# NEJE-KZ-board.net
KiCad netlist of a schematic drawn in EAGLE
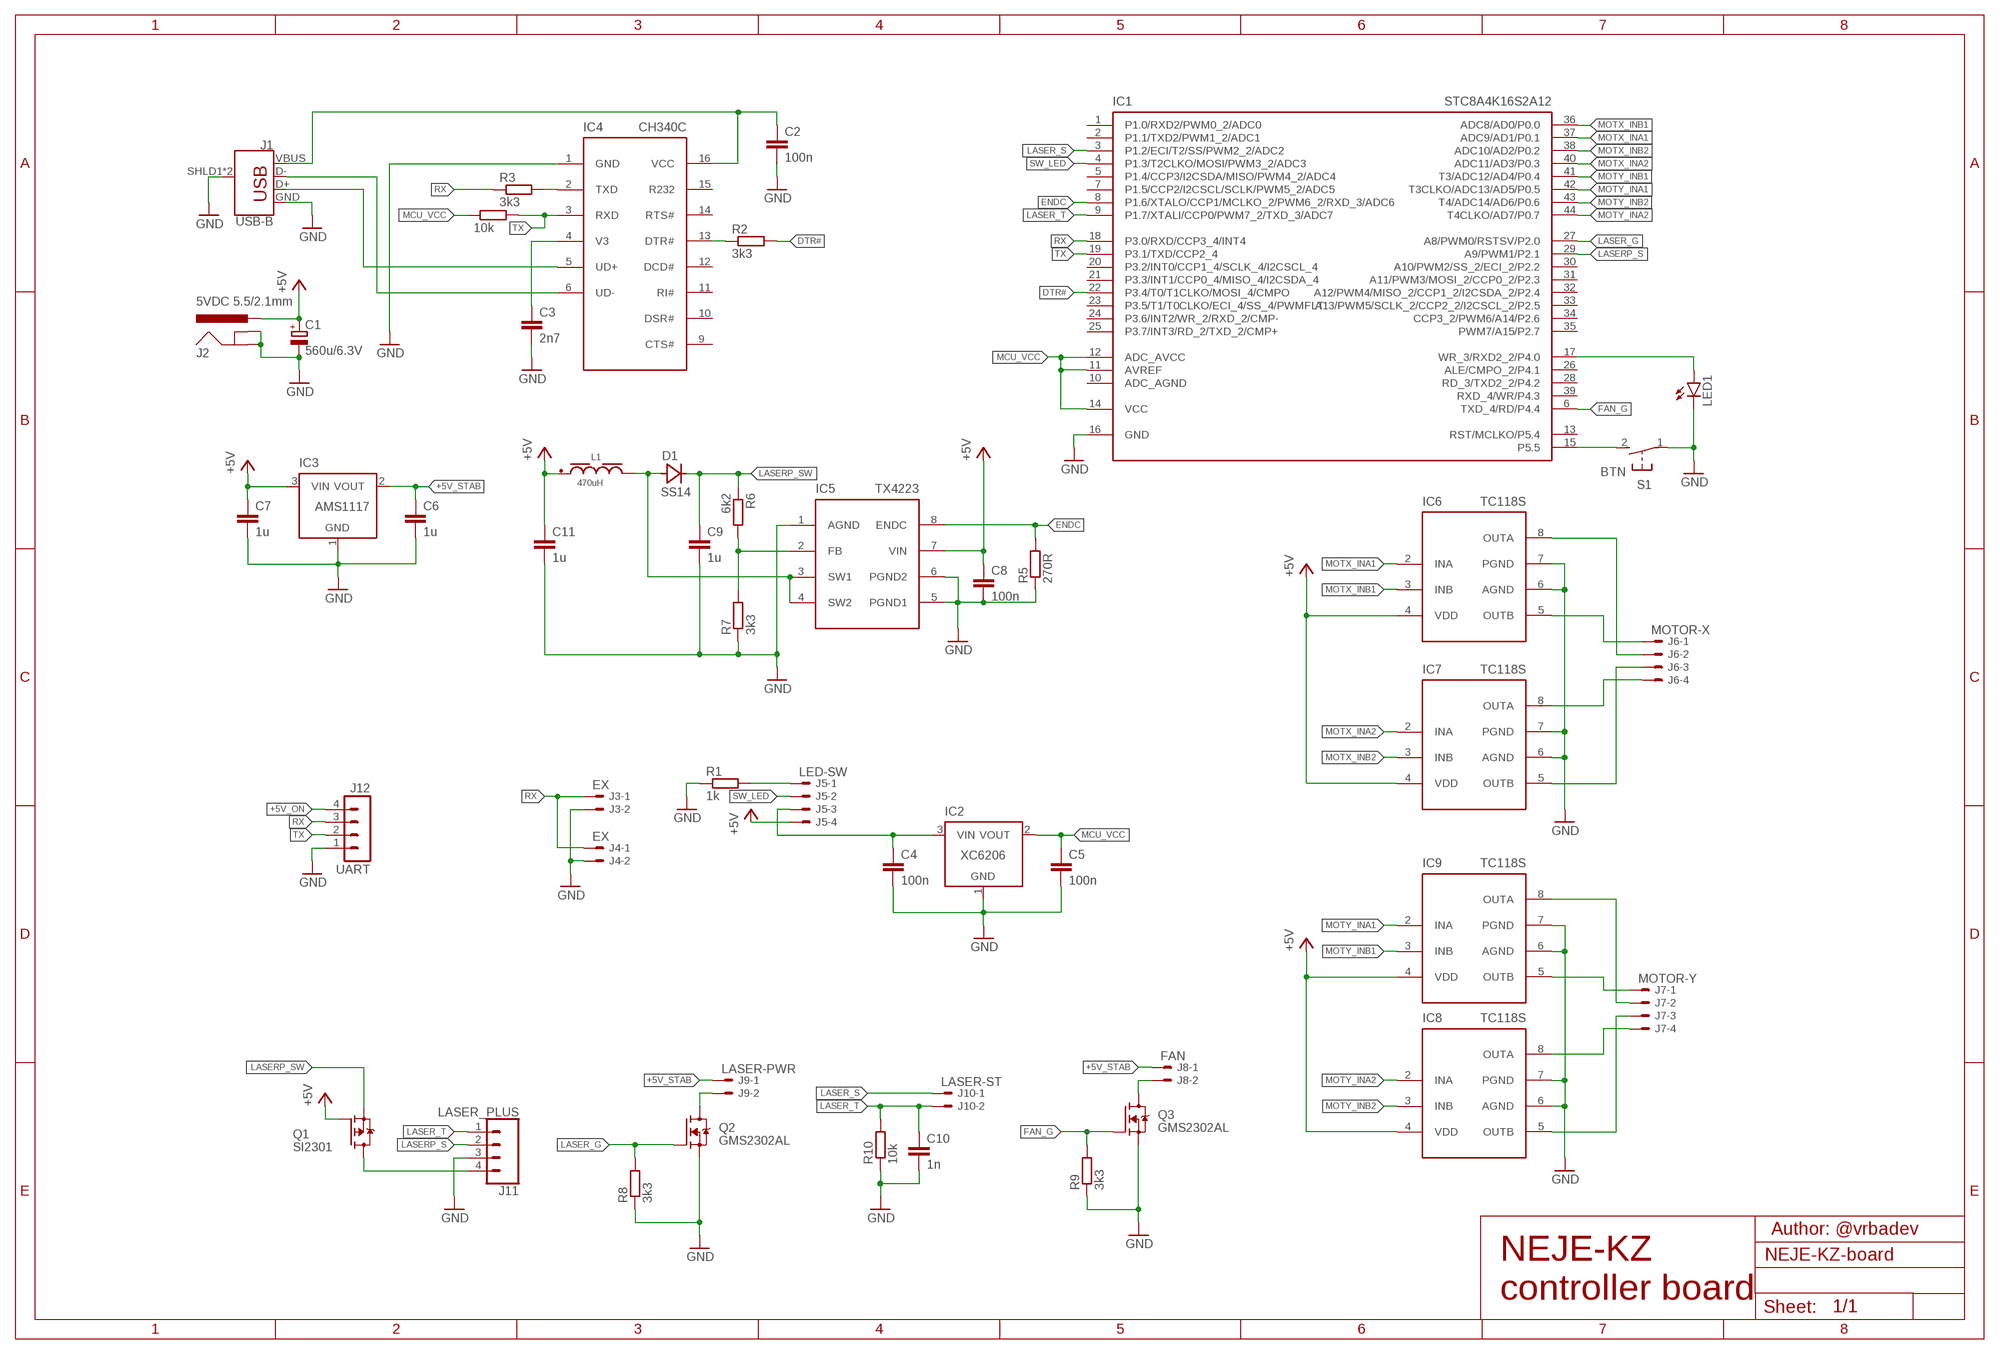
[diagram p0: schematic, sheet 1]

(export (version "E")
  (design (tool "Eeschema 10.0.6"))
  (components
    (comp (ref "C1")
      (value "560u/6.3V")
      (footprint "eagle-import:E2,5-7")
      (libsource (lib "eagle-import") (part "CPOL-EUE2.5-7"))
    )
    (comp (ref "C2")
      (value "100n")
      (footprint "eagle-import:C0402")
      (libsource (lib "eagle-import") (part "C-EUC0402"))
    )
    (comp (ref "C3")
      (value "2n7")
      (footprint "eagle-import:C0402")
      (libsource (lib "eagle-import") (part "C-EUC0402"))
    )
    (comp (ref "C4")
      (value "100n")
      (footprint "eagle-import:C0402")
      (libsource (lib "eagle-import") (part "C-EUC0402"))
    )
    (comp (ref "C5")
      (value "100n")
      (footprint "eagle-import:C0402")
      (libsource (lib "eagle-import") (part "C-EUC0402"))
    )
    (comp (ref "C6")
      (value "1u")
      (footprint "eagle-import:C0603")
      (libsource (lib "eagle-import") (part "C-EUC0603"))
    )
    (comp (ref "C7")
      (value "1u")
      (footprint "eagle-import:C0603")
      (libsource (lib "eagle-import") (part "C-EUC0603"))
    )
    (comp (ref "C8")
      (value "100n")
      (footprint "eagle-import:C0402")
      (libsource (lib "eagle-import") (part "C-EUC0402"))
    )
    (comp (ref "C9")
      (value "1u")
      (footprint "eagle-import:C0805")
      (libsource (lib "eagle-import") (part "C-EUC0805"))
    )
    (comp (ref "C10")
      (value "1n")
      (footprint "eagle-import:C0402")
      (libsource (lib "eagle-import") (part "C-EUC0402"))
    )
    (comp (ref "C11")
      (value "1u")
      (footprint "eagle-import:C0805")
      (libsource (lib "eagle-import") (part "C-EUC0805"))
    )
    (comp (ref "D1")
      (value "SS14")
      (footprint "eagle-import:SMA")
      (libsource (lib "eagle-import") (part "MBRA340T3"))
    )
    (comp (ref "IC1")
      (value "STC8A4K16S2A12")
      (footprint "eagle-import:LQFP44-10X10")
      (libsource (lib "eagle-import") (part "STC8A4K16S2A12"))
    )
    (comp (ref "IC2")
      (value "XC6206")
      (footprint "eagle-import:SOT23-3")
      (libsource (lib "eagle-import") (part "XC6206"))
    )
    (comp (ref "IC3")
      (value "AMS1117")
      (footprint "eagle-import:SOT223")
      (libsource (lib "eagle-import") (part "AMS1117"))
    )
    (comp (ref "IC4")
      (value "CH340C")
      (footprint "eagle-import:SO16")
      (libsource (lib "eagle-import") (part "CH340C"))
    )
    (comp (ref "IC5")
      (value "TX4223")
      (footprint "eagle-import:SOIC8")
      (libsource (lib "eagle-import") (part "TX4223"))
    )
    (comp (ref "IC6")
      (value "TC118S")
      (footprint "eagle-import:SOIC8")
      (libsource (lib "eagle-import") (part "TC118S"))
    )
    (comp (ref "IC7")
      (value "TC118S")
      (footprint "eagle-import:SOIC8")
      (libsource (lib "eagle-import") (part "TC118S"))
    )
    (comp (ref "IC8")
      (value "TC118S")
      (footprint "eagle-import:SOIC8")
      (libsource (lib "eagle-import") (part "TC118S"))
    )
    (comp (ref "IC9")
      (value "TC118S")
      (footprint "eagle-import:SOIC8")
      (libsource (lib "eagle-import") (part "TC118S"))
    )
    (comp (ref "J1")
      (value "USB-B")
      (footprint "eagle-import:USB-B-PTH")
      (libsource (lib "eagle-import") (part "USB_B_PTH"))
    )
    (comp (ref "J2")
      (value "5VDC 5.5/2.1mm")
      (footprint "eagle-import:POWER_JACK_SLOT")
      (libsource (lib "eagle-import") (part "POWER_JACKSLT"))
    )
    (comp (ref "J3")
      (value "EX")
      (footprint "eagle-import:JST-XH-02-PACKAGE-LONG-PAD")
      (libsource (lib "eagle-import") (part "JST-XH-02-PIN-LONG-PAD"))
    )
    (comp (ref "J4")
      (value "EX")
      (footprint "eagle-import:JST-XH-02-PACKAGE-LONG-PAD")
      (libsource (lib "eagle-import") (part "JST-XH-02-PIN-LONG-PAD"))
    )
    (comp (ref "J5")
      (value "LED-SW")
      (footprint "eagle-import:JST-XH-04-PACKAGE-LONG-PAD")
      (libsource (lib "eagle-import") (part "JST-XH-04-PIN-LONG-PAD"))
    )
    (comp (ref "J6")
      (value "MOTOR-X")
      (footprint "eagle-import:JST-XH-04-PACKAGE-LONG-PAD")
      (libsource (lib "eagle-import") (part "JST-XH-04-PIN-LONG-PAD"))
    )
    (comp (ref "J7")
      (value "MOTOR-Y")
      (footprint "eagle-import:JST-XH-04-PACKAGE-LONG-PAD")
      (libsource (lib "eagle-import") (part "JST-XH-04-PIN-LONG-PAD"))
    )
    (comp (ref "J8")
      (value "FAN")
      (footprint "eagle-import:JST-XH-02-PACKAGE-LONG-PAD")
      (libsource (lib "eagle-import") (part "JST-XH-02-PIN-LONG-PAD"))
    )
    (comp (ref "J9")
      (value "LASER-PWR")
      (footprint "eagle-import:JST-XH-02-PACKAGE-LONG-PAD")
      (libsource (lib "eagle-import") (part "JST-XH-02-PIN-LONG-PAD"))
    )
    (comp (ref "J10")
      (value "LASER-ST")
      (footprint "eagle-import:JST-XH-02-PACKAGE-LONG-PAD")
      (libsource (lib "eagle-import") (part "JST-XH-02-PIN-LONG-PAD"))
    )
    (comp (ref "J11")
      (value "LASER_PLUS")
      (footprint "eagle-import:1X04_1MM_RA")
      (libsource (lib "eagle-import") (part "CONN_04SMD2"))
    )
    (comp (ref "J12")
      (value "UART")
      (footprint "eagle-import:MA04-1")
      (libsource (lib "eagle-import") (part "MA04-1"))
    )
    (comp (ref "L1")
      (value "470uH")
      (footprint "eagle-import:WE-PD_7345")
      (libsource (lib "eagle-import") (part "WE-PD_7345_74477724"))
    )
    (comp (ref "LED1")
      (value "LEDCHIP-LED0805")
      (footprint "eagle-import:CHIP-LED0805")
      (libsource (lib "eagle-import") (part "LEDCHIP-LED0805"))
    )
    (comp (ref "Q1")
      (value "SI2301")
      (footprint "eagle-import:SOT23-3")
      (libsource (lib "eagle-import") (part "SI2301"))
    )
    (comp (ref "Q2")
      (value "GMS2302AL")
      (footprint "eagle-import:SOT23-3")
      (libsource (lib "eagle-import") (part "GMS2302AL"))
    )
    (comp (ref "Q3")
      (value "GMS2302AL")
      (footprint "eagle-import:SOT23-3")
      (libsource (lib "eagle-import") (part "GMS2302AL"))
    )
    (comp (ref "R1")
      (value "1k")
      (footprint "eagle-import:R0402")
      (libsource (lib "eagle-import") (part "R-EU_R0402"))
    )
    (comp (ref "R2")
      (value "3k3")
      (footprint "eagle-import:R0402")
      (libsource (lib "eagle-import") (part "R-EU_R0402"))
    )
    (comp (ref "R3")
      (value "3k3")
      (footprint "eagle-import:R0402")
      (libsource (lib "eagle-import") (part "R-EU_R0402"))
    )
    (comp (ref "R4")
      (value "10k")
      (footprint "eagle-import:R0402")
      (libsource (lib "eagle-import") (part "R-EU_R0402"))
    )
    (comp (ref "R5")
      (value "270R")
      (footprint "eagle-import:R0402")
      (libsource (lib "eagle-import") (part "R-EU_R0402"))
    )
    (comp (ref "R6")
      (value "6k2")
      (footprint "eagle-import:R0402")
      (libsource (lib "eagle-import") (part "R-EU_R0402"))
    )
    (comp (ref "R7")
      (value "3k3")
      (footprint "eagle-import:R0402")
      (libsource (lib "eagle-import") (part "R-EU_R0402"))
    )
    (comp (ref "R8")
      (value "3k3")
      (footprint "eagle-import:R0402")
      (libsource (lib "eagle-import") (part "R-EU_R0402"))
    )
    (comp (ref "R9")
      (value "3k3")
      (footprint "eagle-import:R0402")
      (libsource (lib "eagle-import") (part "R-EU_R0402"))
    )
    (comp (ref "R10")
      (value "10k")
      (footprint "eagle-import:R0402")
      (libsource (lib "eagle-import") (part "R-EU_R0402"))
    )
    (comp (ref "S1")
      (value "BTN")
      (footprint "eagle-import:DTSM-3")
      (libsource (lib "eagle-import") (part "DTSM-3"))
    )
  )
  (nets
    (net (code "1") (name "+5V") (class "Default")
      (node (ref "C1") (pin "+") (pinfunction "+_+") (pintype "passive"))
      (node (ref "C11") (pin "1") (pinfunction "1_1") (pintype "passive"))
      (node (ref "C7") (pin "1") (pinfunction "1_1") (pintype "passive"))
      (node (ref "C8") (pin "1") (pinfunction "1_1") (pintype "passive"))
      (node (ref "IC3") (pin "3") (pinfunction "VIN_3") (pintype "passive"))
      (node (ref "IC5") (pin "7") (pinfunction "VIN_7") (pintype "bidirectional"))
      (node (ref "IC6") (pin "4") (pinfunction "VDD_4") (pintype "bidirectional"))
      (node (ref "IC7") (pin "4") (pinfunction "VDD_4") (pintype "bidirectional"))
      (node (ref "IC8") (pin "4") (pinfunction "VDD_4") (pintype "bidirectional"))
      (node (ref "IC9") (pin "4") (pinfunction "VDD_4") (pintype "bidirectional"))
      (node (ref "J2") (pin "PWR") (pinfunction "PWR_PWR") (pintype "power_in"))
      (node (ref "J5") (pin "4") (pinfunction "S_4") (pintype "passive"))
      (node (ref "L1") (pin "1") (pinfunction "1_1") (pintype "passive"))
      (node (ref "Q1") (pin "1") (pinfunction "G_1") (pintype "passive"))
    )
    (net (code "2") (name "+5V_ON") (class "Default")
      (node (ref "C4") (pin "1") (pinfunction "1_1") (pintype "passive"))
      (node (ref "IC2") (pin "3") (pinfunction "VIN_3") (pintype "passive"))
      (node (ref "J12") (pin "4") (pinfunction "4_4") (pintype "passive"))
      (node (ref "J5") (pin "3") (pinfunction "S_3") (pintype "passive"))
    )
    (net (code "3") (name "+5V_STAB") (class "Default")
      (node (ref "C6") (pin "1") (pinfunction "1_1") (pintype "passive"))
      (node (ref "IC3") (pin "2") (pinfunction "VOUT_2") (pintype "output"))
      (node (ref "J8") (pin "1") (pinfunction "S_1") (pintype "passive"))
      (node (ref "J9") (pin "1") (pinfunction "S_1") (pintype "passive"))
    )
    (net (code "4") (name "DTR#") (class "Default")
      (node (ref "IC1") (pin "22") (pinfunction "P3.4/T0/T1CLKO/MOSI_4/CMPO_22") (pintype "bidirectional"))
      (node (ref "R2") (pin "2") (pinfunction "2_2") (pintype "passive"))
    )
    (net (code "5") (name "ENDC") (class "Default")
      (node (ref "IC1") (pin "8") (pinfunction "P1.6/XTALO/CCP1/MCLKO_2/PWM6_2/RXD_3/ADC6_8") (pintype "bidirectional"))
      (node (ref "IC5") (pin "8") (pinfunction "ENDC_8") (pintype "bidirectional"))
      (node (ref "R5") (pin "2") (pinfunction "2_2") (pintype "passive"))
    )
    (net (code "6") (name "FAN_G") (class "Default")
      (node (ref "IC1") (pin "6") (pinfunction "TXD_4/RD/P4.4_6") (pintype "bidirectional"))
      (node (ref "Q3") (pin "1") (pinfunction "G_1") (pintype "passive"))
      (node (ref "R9") (pin "2") (pinfunction "2_2") (pintype "passive"))
    )
    (net (code "7") (name "GND") (class "Default")
      (node (ref "C1") (pin "-") (pinfunction "-_-") (pintype "passive"))
      (node (ref "C10") (pin "2") (pinfunction "2_2") (pintype "passive"))
      (node (ref "C11") (pin "2") (pinfunction "2_2") (pintype "passive"))
      (node (ref "C2") (pin "2") (pinfunction "2_2") (pintype "passive"))
      (node (ref "C3") (pin "2") (pinfunction "2_2") (pintype "passive"))
      (node (ref "C4") (pin "2") (pinfunction "2_2") (pintype "passive"))
      (node (ref "C5") (pin "2") (pinfunction "2_2") (pintype "passive"))
      (node (ref "C6") (pin "2") (pinfunction "2_2") (pintype "passive"))
      (node (ref "C7") (pin "2") (pinfunction "2_2") (pintype "passive"))
      (node (ref "C8") (pin "2") (pinfunction "2_2") (pintype "passive"))
      (node (ref "C9") (pin "2") (pinfunction "2_2") (pintype "passive"))
      (node (ref "IC1") (pin "16") (pinfunction "GND_16") (pintype "bidirectional"))
      (node (ref "IC2") (pin "1") (pinfunction "GND_1") (pintype "power_in"))
      (node (ref "IC3") (pin "1") (pinfunction "GND_1") (pintype "power_in"))
      (node (ref "IC4") (pin "1") (pinfunction "GND_1") (pintype "bidirectional"))
      (node (ref "IC5") (pin "1") (pinfunction "AGND_1") (pintype "bidirectional"))
      (node (ref "IC5") (pin "5") (pinfunction "PGND1_5") (pintype "bidirectional"))
      (node (ref "IC5") (pin "6") (pinfunction "PGND2_6") (pintype "bidirectional"))
      (node (ref "IC6") (pin "6") (pinfunction "AGND_6") (pintype "bidirectional"))
      (node (ref "IC6") (pin "7") (pinfunction "PGND_7") (pintype "bidirectional"))
      (node (ref "IC7") (pin "6") (pinfunction "AGND_6") (pintype "bidirectional"))
      (node (ref "IC7") (pin "7") (pinfunction "PGND_7") (pintype "bidirectional"))
      (node (ref "IC8") (pin "6") (pinfunction "AGND_6") (pintype "bidirectional"))
      (node (ref "IC8") (pin "7") (pinfunction "PGND_7") (pintype "bidirectional"))
      (node (ref "IC9") (pin "6") (pinfunction "AGND_6") (pintype "bidirectional"))
      (node (ref "IC9") (pin "7") (pinfunction "PGND_7") (pintype "bidirectional"))
      (node (ref "J1") (pin "GND") (pinfunction "GND_GND") (pintype "power_in"))
      (node (ref "J1") (pin "SHLD1") (pinfunction "SHIELD_SHLD1") (pintype "bidirectional"))
      (node (ref "J1") (pin "SHLD2") (pinfunction "SHIELD_SHLD2") (pintype "bidirectional"))
      (node (ref "J11") (pin "3") (pinfunction "3_3") (pintype "passive"))
      (node (ref "J12") (pin "1") (pinfunction "1_1") (pintype "passive"))
      (node (ref "J2") (pin "GND@1") (pinfunction "GNDBREAK_GND@1") (pintype "power_in"))
      (node (ref "J2") (pin "GND@2") (pinfunction "GND_GND@2") (pintype "power_in"))
      (node (ref "J3") (pin "2") (pinfunction "S_2") (pintype "passive"))
      (node (ref "J4") (pin "2") (pinfunction "S_2") (pintype "passive"))
      (node (ref "LED1") (pin "C") (pinfunction "C_C") (pintype "passive"))
      (node (ref "Q2") (pin "2") (pinfunction "S_2") (pintype "passive"))
      (node (ref "Q3") (pin "2") (pinfunction "S_2") (pintype "passive"))
      (node (ref "R1") (pin "1") (pinfunction "1_1") (pintype "passive"))
      (node (ref "R10") (pin "1") (pinfunction "1_1") (pintype "passive"))
      (node (ref "R5") (pin "1") (pinfunction "1_1") (pintype "passive"))
      (node (ref "R7") (pin "1") (pinfunction "1_1") (pintype "passive"))
      (node (ref "R8") (pin "1") (pinfunction "1_1") (pintype "passive"))
      (node (ref "R9") (pin "1") (pinfunction "1_1") (pintype "passive"))
      (node (ref "S1") (pin "1") (pinfunction "1_1") (pintype "passive"))
    )
    (net (code "8") (name "LASERP_S") (class "Default")
      (node (ref "IC1") (pin "29") (pinfunction "A9/PWM1/P2.1_29") (pintype "bidirectional"))
      (node (ref "J11") (pin "2") (pinfunction "2_2") (pintype "passive"))
    )
    (net (code "9") (name "LASERP_SW") (class "Default")
      (node (ref "C9") (pin "1") (pinfunction "1_1") (pintype "passive"))
      (node (ref "D1") (pin "C") (pinfunction "C_C") (pintype "passive"))
      (node (ref "Q1") (pin "2") (pinfunction "S_2") (pintype "passive"))
      (node (ref "R6") (pin "1") (pinfunction "1_1") (pintype "passive"))
    )
    (net (code "10") (name "LASER_G") (class "Default")
      (node (ref "IC1") (pin "27") (pinfunction "A8/PWM0/RSTSV/P2.0_27") (pintype "bidirectional"))
      (node (ref "Q2") (pin "1") (pinfunction "G_1") (pintype "passive"))
      (node (ref "R8") (pin "2") (pinfunction "2_2") (pintype "passive"))
    )
    (net (code "11") (name "LASER_S") (class "Default")
      (node (ref "IC1") (pin "3") (pinfunction "P1.2/ECI/T2/SS/PWM2_2/ADC2_3") (pintype "bidirectional"))
      (node (ref "J10") (pin "1") (pinfunction "S_1") (pintype "passive"))
    )
    (net (code "12") (name "LASER_T") (class "Default")
      (node (ref "C10") (pin "1") (pinfunction "1_1") (pintype "passive"))
      (node (ref "IC1") (pin "9") (pinfunction "P1.7/XTALI/CCP0/PWM7_2/TXD_3/ADC7_9") (pintype "bidirectional"))
      (node (ref "J10") (pin "2") (pinfunction "S_2") (pintype "passive"))
      (node (ref "J11") (pin "1") (pinfunction "1_1") (pintype "passive"))
      (node (ref "R10") (pin "2") (pinfunction "2_2") (pintype "passive"))
    )
    (net (code "13") (name "MCU_VCC") (class "Default")
      (node (ref "C5") (pin "1") (pinfunction "1_1") (pintype "passive"))
      (node (ref "IC1") (pin "11") (pinfunction "AVREF_11") (pintype "bidirectional"))
      (node (ref "IC1") (pin "12") (pinfunction "ADC_AVCC_12") (pintype "bidirectional"))
      (node (ref "IC1") (pin "14") (pinfunction "VCC_14") (pintype "bidirectional"))
      (node (ref "IC2") (pin "2") (pinfunction "VOUT_2") (pintype "output"))
      (node (ref "R4") (pin "1") (pinfunction "1_1") (pintype "passive"))
    )
    (net (code "14") (name "MOTX_INA1") (class "Default")
      (node (ref "IC1") (pin "37") (pinfunction "ADC9/AD1/P0.1_37") (pintype "bidirectional"))
      (node (ref "IC6") (pin "2") (pinfunction "INA_2") (pintype "bidirectional"))
    )
    (net (code "15") (name "MOTX_INA2") (class "Default")
      (node (ref "IC1") (pin "40") (pinfunction "ADC11/AD3/P0.3_40") (pintype "bidirectional"))
      (node (ref "IC7") (pin "2") (pinfunction "INA_2") (pintype "bidirectional"))
    )
    (net (code "16") (name "MOTX_INB1") (class "Default")
      (node (ref "IC1") (pin "36") (pinfunction "ADC8/AD0/P0.0_36") (pintype "bidirectional"))
      (node (ref "IC6") (pin "3") (pinfunction "INB_3") (pintype "bidirectional"))
    )
    (net (code "17") (name "MOTX_INB2") (class "Default")
      (node (ref "IC1") (pin "38") (pinfunction "ADC10/AD2/P0.2_38") (pintype "bidirectional"))
      (node (ref "IC7") (pin "3") (pinfunction "INB_3") (pintype "bidirectional"))
    )
    (net (code "18") (name "MOTY_INA1") (class "Default")
      (node (ref "IC1") (pin "42") (pinfunction "T3CLKO/ADC13/AD5/P0.5_42") (pintype "bidirectional"))
      (node (ref "IC9") (pin "2") (pinfunction "INA_2") (pintype "bidirectional"))
    )
    (net (code "19") (name "MOTY_INA2") (class "Default")
      (node (ref "IC1") (pin "44") (pinfunction "T4CLKO/AD7/P0.7_44") (pintype "bidirectional"))
      (node (ref "IC8") (pin "2") (pinfunction "INA_2") (pintype "bidirectional"))
    )
    (net (code "20") (name "MOTY_INB1") (class "Default")
      (node (ref "IC1") (pin "41") (pinfunction "T3/ADC12/AD4/P0.4_41") (pintype "bidirectional"))
      (node (ref "IC9") (pin "3") (pinfunction "INB_3") (pintype "bidirectional"))
    )
    (net (code "21") (name "MOTY_INB2") (class "Default")
      (node (ref "IC1") (pin "43") (pinfunction "T4/ADC14/AD6/P0.6_43") (pintype "bidirectional"))
      (node (ref "IC8") (pin "3") (pinfunction "INB_3") (pintype "bidirectional"))
    )
    (net (code "22") (name "Net-(IC1-P5.5)") (class "Default")
      (node (ref "IC1") (pin "15") (pinfunction "P5.5_15") (pintype "bidirectional"))
      (node (ref "S1") (pin "2") (pinfunction "2_2") (pintype "passive"))
    )
    (net (code "23") (name "Net-(IC1-WR_3{slash}RXD2_2{slash}P4.0)") (class "Default")
      (node (ref "IC1") (pin "17") (pinfunction "WR_3/RXD2_2/P4.0_17") (pintype "bidirectional"))
      (node (ref "LED1") (pin "A") (pinfunction "A_A") (pintype "passive"))
    )
    (net (code "24") (name "Net-(IC4-DTR#)") (class "Default")
      (node (ref "IC4") (pin "13") (pinfunction "DTR#_13") (pintype "bidirectional"))
      (node (ref "R2") (pin "1") (pinfunction "1_1") (pintype "passive"))
    )
    (net (code "25") (name "Net-(IC4-TXD)") (class "Default")
      (node (ref "IC4") (pin "2") (pinfunction "TXD_2") (pintype "bidirectional"))
      (node (ref "R3") (pin "2") (pinfunction "2_2") (pintype "passive"))
    )
    (net (code "26") (name "Net-(IC4-UD+)") (class "Default")
      (node (ref "IC4") (pin "5") (pinfunction "UD+_5") (pintype "bidirectional"))
      (node (ref "J1") (pin "D+") (pinfunction "D+_D+") (pintype "bidirectional"))
    )
    (net (code "27") (name "Net-(IC4-UD-)") (class "Default")
      (node (ref "IC4") (pin "6") (pinfunction "UD-_6") (pintype "bidirectional"))
      (node (ref "J1") (pin "D-") (pinfunction "D-_D-") (pintype "bidirectional"))
    )
    (net (code "28") (name "Net-(IC4-V3)") (class "Default")
      (node (ref "C3") (pin "1") (pinfunction "1_1") (pintype "passive"))
      (node (ref "IC4") (pin "4") (pinfunction "V3_4") (pintype "bidirectional"))
    )
    (net (code "29") (name "Net-(IC4-VCC)") (class "Default")
      (node (ref "C2") (pin "1") (pinfunction "1_1") (pintype "passive"))
      (node (ref "IC4") (pin "16") (pinfunction "VCC_16") (pintype "bidirectional"))
      (node (ref "J1") (pin "VBUS") (pinfunction "VBUS_VBUS") (pintype "power_in"))
    )
    (net (code "30") (name "Net-(IC5-FB)") (class "Default")
      (node (ref "IC5") (pin "2") (pinfunction "FB_2") (pintype "bidirectional"))
      (node (ref "R6") (pin "2") (pinfunction "2_2") (pintype "passive"))
      (node (ref "R7") (pin "2") (pinfunction "2_2") (pintype "passive"))
    )
    (net (code "31") (name "Net-(IC5-SW1)") (class "Default")
      (node (ref "D1") (pin "A") (pinfunction "A_A") (pintype "passive"))
      (node (ref "IC5") (pin "3") (pinfunction "SW1_3") (pintype "bidirectional"))
      (node (ref "IC5") (pin "4") (pinfunction "SW2_4") (pintype "bidirectional"))
      (node (ref "L1") (pin "2") (pinfunction "2_2") (pintype "passive"))
    )
    (net (code "32") (name "Net-(IC6-OUTA)") (class "Default")
      (node (ref "IC6") (pin "8") (pinfunction "OUTA_8") (pintype "bidirectional"))
      (node (ref "J6") (pin "2") (pinfunction "S_2") (pintype "passive"))
    )
    (net (code "33") (name "Net-(IC6-OUTB)") (class "Default")
      (node (ref "IC6") (pin "5") (pinfunction "OUTB_5") (pintype "bidirectional"))
      (node (ref "J6") (pin "1") (pinfunction "S_1") (pintype "passive"))
    )
    (net (code "34") (name "Net-(IC7-OUTA)") (class "Default")
      (node (ref "IC7") (pin "8") (pinfunction "OUTA_8") (pintype "bidirectional"))
      (node (ref "J6") (pin "4") (pinfunction "S_4") (pintype "passive"))
    )
    (net (code "35") (name "Net-(IC7-OUTB)") (class "Default")
      (node (ref "IC7") (pin "5") (pinfunction "OUTB_5") (pintype "bidirectional"))
      (node (ref "J6") (pin "3") (pinfunction "S_3") (pintype "passive"))
    )
    (net (code "36") (name "Net-(IC8-OUTA)") (class "Default")
      (node (ref "IC8") (pin "8") (pinfunction "OUTA_8") (pintype "bidirectional"))
      (node (ref "J7") (pin "4") (pinfunction "S_4") (pintype "passive"))
    )
    (net (code "37") (name "Net-(IC8-OUTB)") (class "Default")
      (node (ref "IC8") (pin "5") (pinfunction "OUTB_5") (pintype "bidirectional"))
      (node (ref "J7") (pin "3") (pinfunction "S_3") (pintype "passive"))
    )
    (net (code "38") (name "Net-(IC9-OUTA)") (class "Default")
      (node (ref "IC9") (pin "8") (pinfunction "OUTA_8") (pintype "bidirectional"))
      (node (ref "J7") (pin "2") (pinfunction "S_2") (pintype "passive"))
    )
    (net (code "39") (name "Net-(IC9-OUTB)") (class "Default")
      (node (ref "IC9") (pin "5") (pinfunction "OUTB_5") (pintype "bidirectional"))
      (node (ref "J7") (pin "1") (pinfunction "S_1") (pintype "passive"))
    )
    (net (code "40") (name "Net-(J5A-S)") (class "Default")
      (node (ref "J5") (pin "1") (pinfunction "S_1") (pintype "passive"))
      (node (ref "R1") (pin "2") (pinfunction "2_2") (pintype "passive"))
    )
    (net (code "41") (name "Net-(J8B-S)") (class "Default")
      (node (ref "J8") (pin "2") (pinfunction "S_2") (pintype "passive"))
      (node (ref "Q3") (pin "3") (pinfunction "D_3") (pintype "passive"))
    )
    (net (code "42") (name "Net-(J9B-S)") (class "Default")
      (node (ref "J9") (pin "2") (pinfunction "S_2") (pintype "passive"))
      (node (ref "Q2") (pin "3") (pinfunction "D_3") (pintype "passive"))
    )
    (net (code "43") (name "Net-(Q1-D)") (class "Default")
      (node (ref "J11") (pin "4") (pinfunction "4_4") (pintype "passive"))
      (node (ref "Q1") (pin "3") (pinfunction "D_3") (pintype "passive"))
    )
    (net (code "44") (name "RX") (class "Default")
      (node (ref "IC1") (pin "18") (pinfunction "P3.0/RXD/CCP3_4/INT4_18") (pintype "bidirectional"))
      (node (ref "J12") (pin "3") (pinfunction "3_3") (pintype "passive"))
      (node (ref "J3") (pin "1") (pinfunction "S_1") (pintype "passive"))
      (node (ref "J4") (pin "1") (pinfunction "S_1") (pintype "passive"))
      (node (ref "R3") (pin "1") (pinfunction "1_1") (pintype "passive"))
    )
    (net (code "45") (name "SW_LED") (class "Default")
      (node (ref "IC1") (pin "4") (pinfunction "P1.3/T2CLKO/MOSI/PWM3_2/ADC3_4") (pintype "bidirectional"))
      (node (ref "J5") (pin "2") (pinfunction "S_2") (pintype "passive"))
    )
    (net (code "46") (name "TX") (class "Default")
      (node (ref "IC1") (pin "19") (pinfunction "P3.1/TXD/CCP2_4_19") (pintype "bidirectional"))
      (node (ref "IC4") (pin "3") (pinfunction "RXD_3") (pintype "bidirectional"))
      (node (ref "J12") (pin "2") (pinfunction "2_2") (pintype "passive"))
      (node (ref "R4") (pin "2") (pinfunction "2_2") (pintype "passive"))
    )
    (net (code "47") (name "unconnected-(IC1-A10{slash}PWM2{slash}SS_2{slash}ECI_2{slash}P2.2-Pad30)") (class "Default")
      (node (ref "IC1") (pin "30") (pinfunction "A10/PWM2/SS_2/ECI_2/P2.2_30") (pintype "bidirectional"))
    )
    (net (code "48") (name "unconnected-(IC1-A11{slash}PWM3{slash}MOSI_2{slash}CCP0_2{slash}P2.3-Pad31)") (class "Default")
      (node (ref "IC1") (pin "31") (pinfunction "A11/PWM3/MOSI_2/CCP0_2/P2.3_31") (pintype "bidirectional"))
    )
    (net (code "49") (name "unconnected-(IC1-A12{slash}PWM4{slash}MISO_2{slash}CCP1_2{slash}I2CSDA_2{slash}P2.4-Pad32)") (class "Default")
      (node (ref "IC1") (pin "32") (pinfunction "A12/PWM4/MISO_2/CCP1_2/I2CSDA_2/P2.4_32") (pintype "bidirectional"))
    )
    (net (code "50") (name "unconnected-(IC1-A13{slash}PWM5{slash}SCLK_2{slash}CCP2_2{slash}I2CSCL_2{slash}P2.5-Pad33)") (class "Default")
      (node (ref "IC1") (pin "33") (pinfunction "A13/PWM5/SCLK_2/CCP2_2/I2CSCL_2/P2.5_33") (pintype "bidirectional"))
    )
    (net (code "51") (name "unconnected-(IC1-ADC_AGND-Pad10)") (class "Default")
      (node (ref "IC1") (pin "10") (pinfunction "ADC_AGND_10") (pintype "bidirectional"))
    )
    (net (code "52") (name "unconnected-(IC1-ALE{slash}CMPO_2{slash}P4.1-Pad26)") (class "Default")
      (node (ref "IC1") (pin "26") (pinfunction "ALE/CMPO_2/P4.1_26") (pintype "bidirectional"))
    )
    (net (code "53") (name "unconnected-(IC1-CCP3_2{slash}PWM6{slash}A14{slash}P2.6-Pad34)") (class "Default")
      (node (ref "IC1") (pin "34") (pinfunction "CCP3_2/PWM6/A14/P2.6_34") (pintype "bidirectional"))
    )
    (net (code "54") (name "unconnected-(IC1-P1.0{slash}RXD2{slash}PWM0_2{slash}ADC0-Pad1)") (class "Default")
      (node (ref "IC1") (pin "1") (pinfunction "P1.0/RXD2/PWM0_2/ADC0_1") (pintype "bidirectional"))
    )
    (net (code "55") (name "unconnected-(IC1-P1.1{slash}TXD2{slash}PWM1_2{slash}ADC1-Pad2)") (class "Default")
      (node (ref "IC1") (pin "2") (pinfunction "P1.1/TXD2/PWM1_2/ADC1_2") (pintype "bidirectional"))
    )
    (net (code "56") (name "unconnected-(IC1-P1.4{slash}CCP3{slash}I2CSDA{slash}MISO{slash}PWM4_2{slash}ADC4-Pad5)") (class "Default")
      (node (ref "IC1") (pin "5") (pinfunction "P1.4/CCP3/I2CSDA/MISO/PWM4_2/ADC4_5") (pintype "bidirectional"))
    )
    (net (code "57") (name "unconnected-(IC1-P1.5{slash}CCP2{slash}I2CSCL{slash}SCLK{slash}PWM5_2{slash}ADC5-Pad7)") (class "Default")
      (node (ref "IC1") (pin "7") (pinfunction "P1.5/CCP2/I2CSCL/SCLK/PWM5_2/ADC5_7") (pintype "bidirectional"))
    )
    (net (code "58") (name "unconnected-(IC1-P3.2{slash}INT0{slash}CCP1_4{slash}SCLK_4{slash}I2CSCL_4-Pad20)") (class "Default")
      (node (ref "IC1") (pin "20") (pinfunction "P3.2/INT0/CCP1_4/SCLK_4/I2CSCL_4_20") (pintype "bidirectional"))
    )
    (net (code "59") (name "unconnected-(IC1-P3.3{slash}INT1{slash}CCP0_4{slash}MISO_4{slash}I2CSDA_4-Pad21)") (class "Default")
      (node (ref "IC1") (pin "21") (pinfunction "P3.3/INT1/CCP0_4/MISO_4/I2CSDA_4_21") (pintype "bidirectional"))
    )
    (net (code "60") (name "unconnected-(IC1-P3.5{slash}T1{slash}T0CLKO{slash}ECI_4{slash}SS_4{slash}PWMFLT-Pad23)") (class "Default")
      (node (ref "IC1") (pin "23") (pinfunction "P3.5/T1/T0CLKO/ECI_4/SS_4/PWMFLT_23") (pintype "bidirectional"))
    )
    (net (code "61") (name "unconnected-(IC1-P3.6{slash}INT2{slash}WR_2{slash}RXD_2{slash}CMP--Pad24)") (class "Default")
      (node (ref "IC1") (pin "24") (pinfunction "P3.6/INT2/WR_2/RXD_2/CMP-_24") (pintype "bidirectional"))
    )
    (net (code "62") (name "unconnected-(IC1-P3.7{slash}INT3{slash}RD_2{slash}TXD_2{slash}CMP+-Pad25)") (class "Default")
      (node (ref "IC1") (pin "25") (pinfunction "P3.7/INT3/RD_2/TXD_2/CMP+_25") (pintype "bidirectional"))
    )
    (net (code "63") (name "unconnected-(IC1-PWM7{slash}A15{slash}P2.7-Pad35)") (class "Default")
      (node (ref "IC1") (pin "35") (pinfunction "PWM7/A15/P2.7_35") (pintype "bidirectional"))
    )
    (net (code "64") (name "unconnected-(IC1-RD_3{slash}TXD2_2{slash}P4.2-Pad28)") (class "Default")
      (node (ref "IC1") (pin "28") (pinfunction "RD_3/TXD2_2/P4.2_28") (pintype "bidirectional"))
    )
    (net (code "65") (name "unconnected-(IC1-RST{slash}MCLKO{slash}P5.4-Pad13)") (class "Default")
      (node (ref "IC1") (pin "13") (pinfunction "RST/MCLKO/P5.4_13") (pintype "bidirectional"))
    )
    (net (code "66") (name "unconnected-(IC1-RXD_4{slash}WR{slash}P4.3-Pad39)") (class "Default")
      (node (ref "IC1") (pin "39") (pinfunction "RXD_4/WR/P4.3_39") (pintype "bidirectional"))
    )
    (net (code "67") (name "unconnected-(IC4-CTS#-Pad9)") (class "Default")
      (node (ref "IC4") (pin "9") (pinfunction "CTS#_9") (pintype "bidirectional"))
    )
    (net (code "68") (name "unconnected-(IC4-DCD#-Pad12)") (class "Default")
      (node (ref "IC4") (pin "12") (pinfunction "DCD#_12") (pintype "bidirectional"))
    )
    (net (code "69") (name "unconnected-(IC4-DSR#-Pad10)") (class "Default")
      (node (ref "IC4") (pin "10") (pinfunction "DSR#_10") (pintype "bidirectional"))
    )
    (net (code "70") (name "unconnected-(IC4-R232-Pad15)") (class "Default")
      (node (ref "IC4") (pin "15") (pinfunction "R232_15") (pintype "bidirectional"))
    )
    (net (code "71") (name "unconnected-(IC4-RI#-Pad11)") (class "Default")
      (node (ref "IC4") (pin "11") (pinfunction "RI#_11") (pintype "bidirectional"))
    )
    (net (code "72") (name "unconnected-(IC4-RTS#-Pad14)") (class "Default")
      (node (ref "IC4") (pin "14") (pinfunction "RTS#_14") (pintype "bidirectional"))
    )
  )
)
